# SysController.net
KiCad netlist of a schematic drawn in Altium Designer
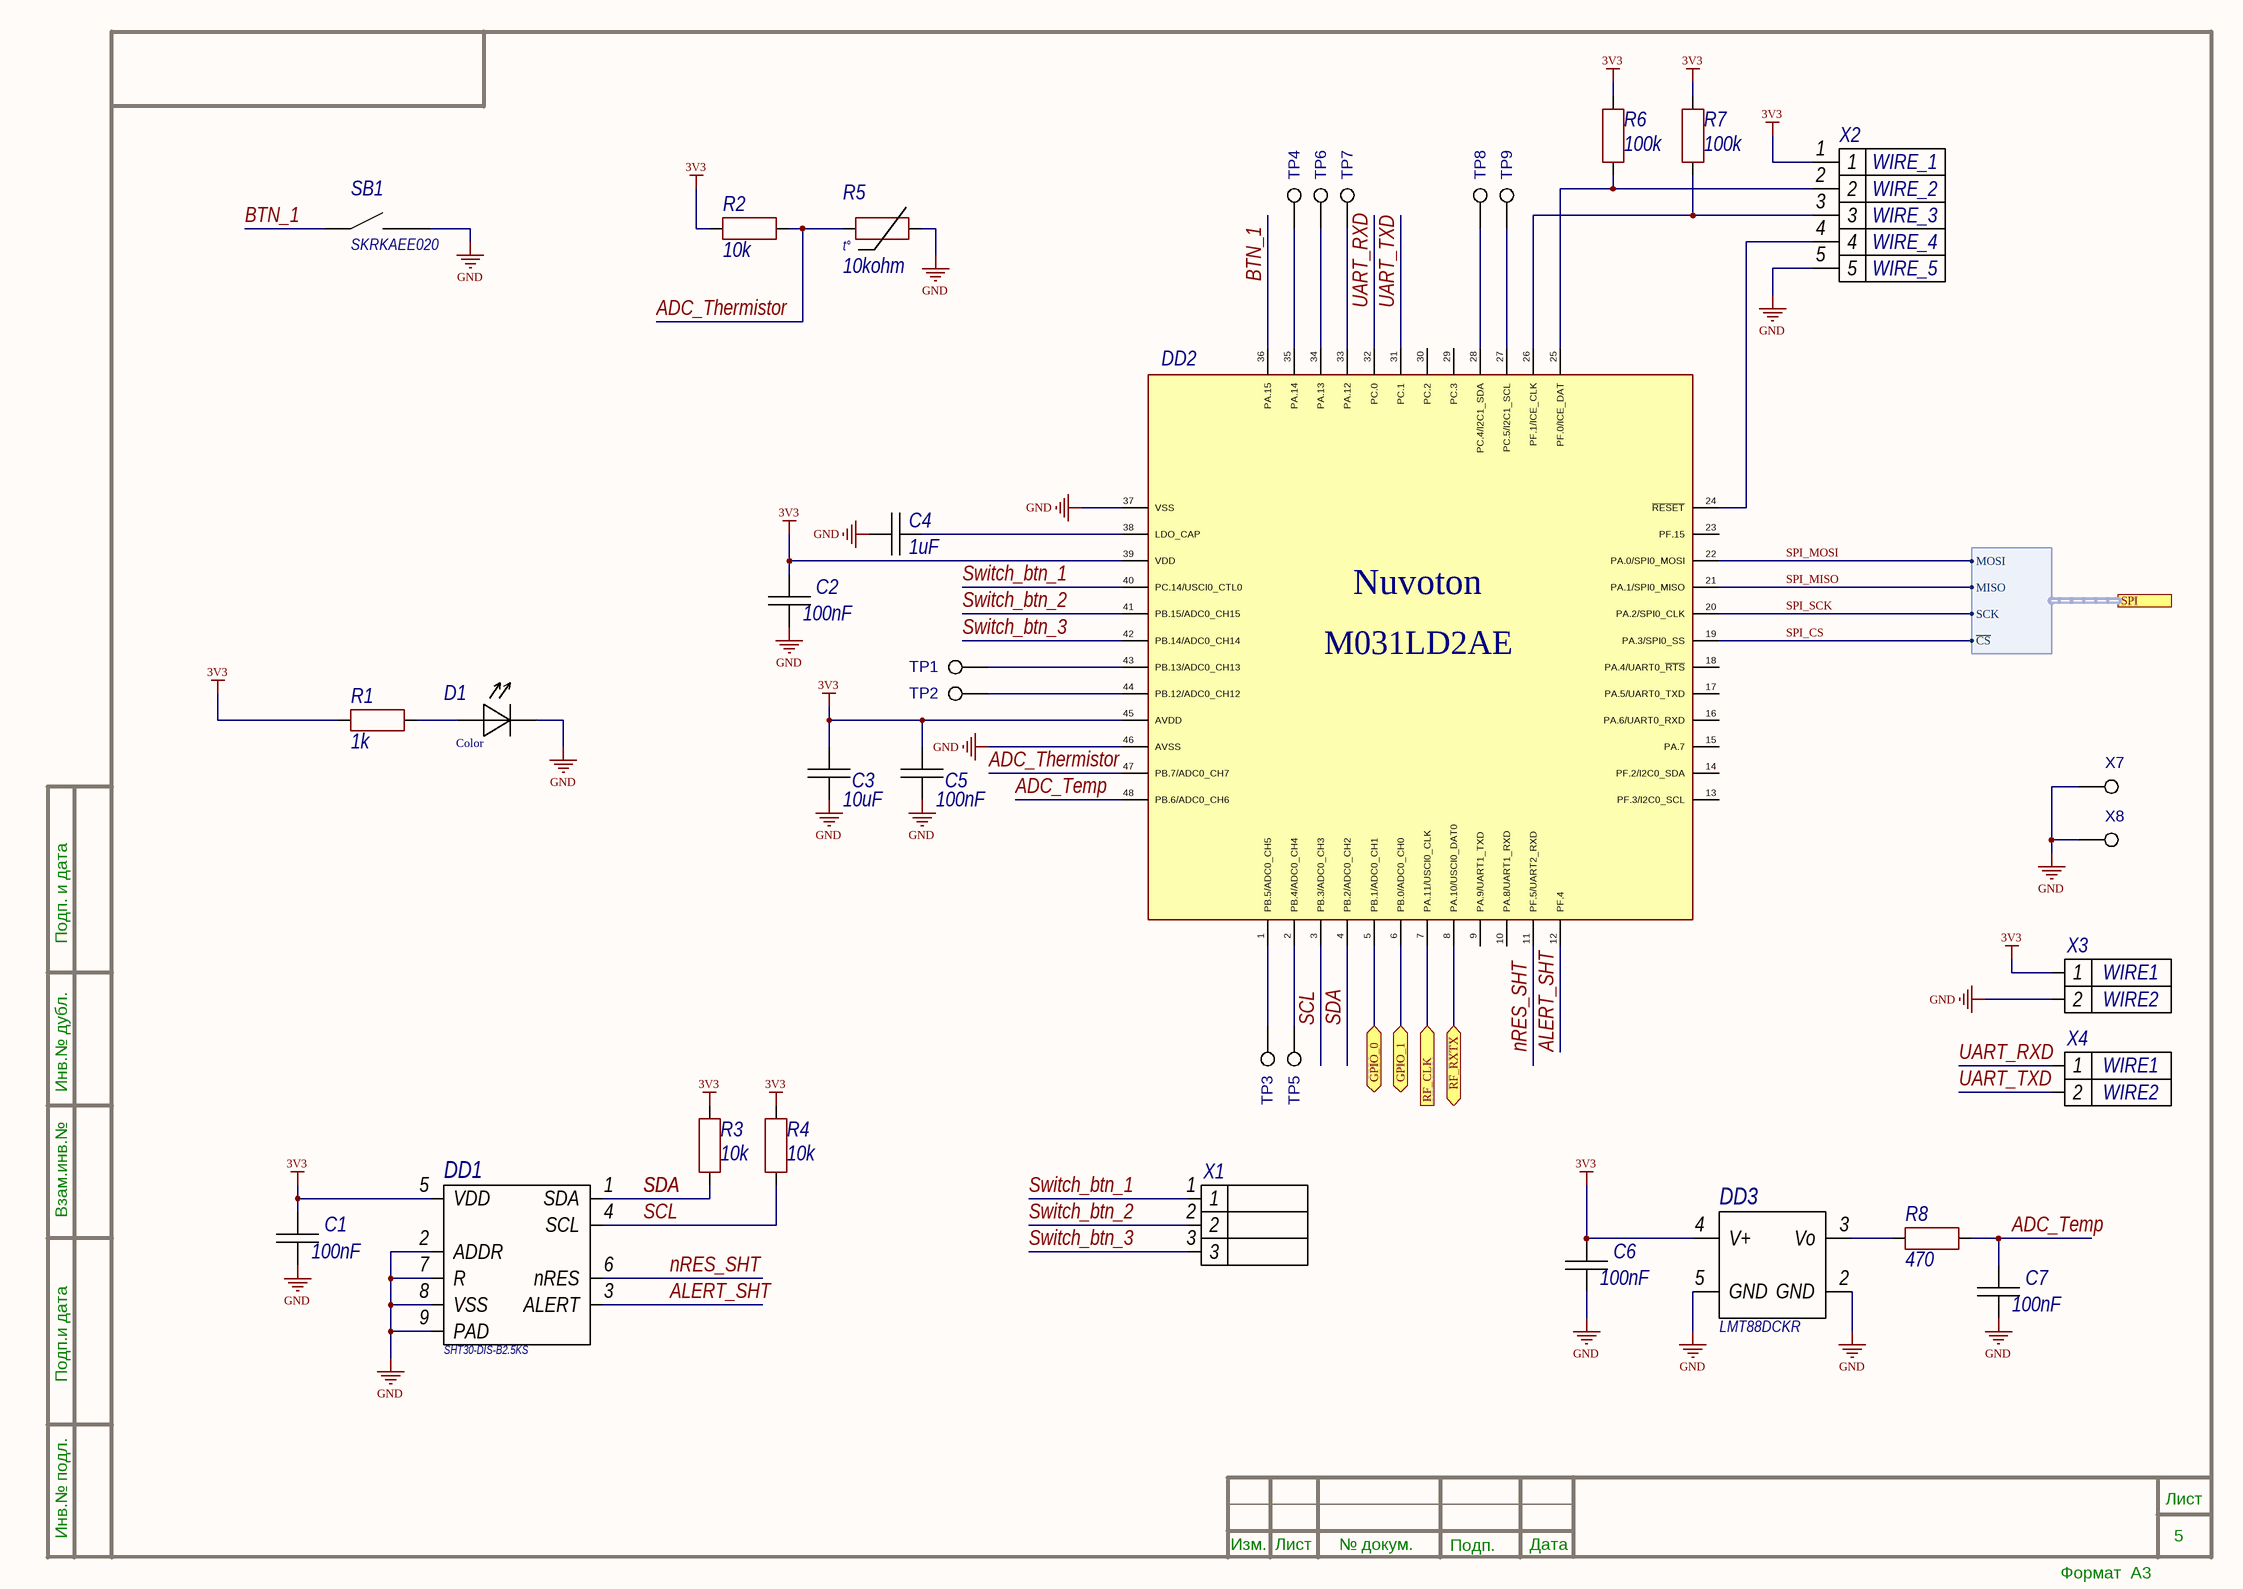
[diagram p0: SysController.SchDoc]

(export (version "E")
  (design (tool "Eeschema 10.0.6"))
  (components
    (comp (ref "C1")
      (value "100nF")
      (footprint "CAP0402")
      (fields (field (name "PART NUMBER") "CAP0402") (field (name "Comment") "100nF "))
      (libsource (lib "Library") (part "CAPC"))
    )
    (comp (ref "C2")
      (value "100nF")
      (footprint "CAP0402")
      (fields (field (name "PART NUMBER") "CAP0402") (field (name "Comment") "100nF "))
      (libsource (lib "Library") (part "CAPC"))
    )
    (comp (ref "C3")
      (value "10uF")
      (footprint "CAPC0603N")
      (fields (field (name "PART NUMBER") "CAPC") (field (name "Comment") "10uF "))
      (libsource (lib "Library") (part "CAPC"))
    )
    (comp (ref "C4")
      (value "1uF")
      (footprint "CAPC0603N")
      (fields (field (name "PART NUMBER") "CAPC") (field (name "Comment") "1uF "))
      (libsource (lib "Library") (part "CAPC"))
    )
    (comp (ref "C5")
      (value "100nF")
      (footprint "CAP0402")
      (fields (field (name "PART NUMBER") "CAP0402") (field (name "Comment") "100nF "))
      (libsource (lib "Library") (part "CAPC"))
    )
    (comp (ref "C6")
      (value "100nF")
      (footprint "CAP0402")
      (fields (field (name "PART NUMBER") "CAP0402") (field (name "Comment") "100nF "))
      (libsource (lib "Library") (part "CAPC"))
    )
    (comp (ref "C7")
      (value "100nF")
      (footprint "CAP0402")
      (fields (field (name "PART NUMBER") "CAP0402") (field (name "Comment") "100nF "))
      (libsource (lib "Library") (part "CAPC"))
    )
    (comp (ref "D1")
      (value "Color")
      (footprint "LED603")
      (fields (field (name "PART NUMBER") "LEDC"))
      (libsource (lib "Library") (part "LEDC"))
    )
    (comp (ref "DD1")
      (value "SHT30-DIS-B2.5KS")
      (footprint "DFN8")
      (fields (field (name "MPN") "SHT30-DIS-B2.5KS") (field (name "MANUFACTURER") "SENSIRION"))
      (libsource (lib "Library") (part "DD_SHTxx"))
    )
    (comp (ref "DD2")
      (value "~")
      (footprint "LQFP48")
      (fields (field (name "PART NUMBER") "M031LD2AE") (field (name "MANUFACTURER") "Nuvoton"))
      (libsource (lib "Library") (part "M031LD2AE"))
    )
    (comp (ref "DD3")
      (value "~")
      (footprint "SC70-5")
      (fields
        (field (name "MPN") "LMT88DCKR")
        (field (name "PART NUMBER") "LMT88DCKR")
        (field (name "MANUFACTURER") "TI")
      )
      (libsource (lib "Library") (part "DD_LMT88"))
    )
    (comp (ref "R1")
      (value "1k")
      (footprint "RESC0402(1005)_M")
      (fields (field (name "PART NUMBER") "RES0402") (field (name "Comment") "1k "))
      (libsource (lib "Library") (part "RES"))
    )
    (comp (ref "R2")
      (value "10k")
      (footprint "RESC0402(1005)_M")
      (fields (field (name "PART NUMBER") "RES0402") (field (name "Comment") "10k "))
      (libsource (lib "Library") (part "RES"))
    )
    (comp (ref "R3")
      (value "10k")
      (footprint "RESC0402(1005)_M")
      (fields (field (name "PART NUMBER") "RES0402") (field (name "Comment") "10k "))
      (libsource (lib "") (part "RES_1"))
    )
    (comp (ref "R4")
      (value "10k")
      (footprint "RESC0402(1005)_M")
      (fields (field (name "PART NUMBER") "RES0402") (field (name "Comment") "10k "))
      (libsource (lib "") (part "RES_1"))
    )
    (comp (ref "R5")
      (value "10kohm")
      (footprint "RESC0805L")
      (fields
        (field (name "PART NUMBER") "SDNT2012X103F3950FTF")
        (field (name "MANUFACTURER") "Sunlord")
        (field (name "Comment") "10kohm ")
      )
      (libsource (lib "Library") (part "RES_Thermo"))
    )
    (comp (ref "R6")
      (value "100k")
      (footprint "RESC0402(1005)_M")
      (fields (field (name "PART NUMBER") "RES0402") (field (name "Comment") "100k "))
      (libsource (lib "") (part "RES_1"))
    )
    (comp (ref "R7")
      (value "100k")
      (footprint "RESC0402(1005)_M")
      (fields (field (name "PART NUMBER") "RES0402") (field (name "Comment") "100k "))
      (libsource (lib "") (part "RES_1"))
    )
    (comp (ref "R8")
      (value "470")
      (footprint "RESC0402(1005)_M")
      (fields (field (name "PART NUMBER") "RES0402") (field (name "Comment") "470 "))
      (libsource (lib "Library") (part "RES"))
    )
    (comp (ref "SB1")
      (value "DTSM-3")
      (footprint "SW_SKRKAEE020")
      (fields (field (name "MPN") "SKRKAEE020") (field (name "PART NUMBER") "SKRKAEE020"))
      (libsource (lib "Library") (part "DTSM-3"))
    )
    (comp (ref "TP1")
      (value "TP-SINGLE-ROUND")
      (footprint "TP-ROUND-TOP-1.5")
      (libsource (lib "Library") (part "TP-SINGLE-ROUND"))
    )
    (comp (ref "TP2")
      (value "TP-SINGLE-ROUND")
      (footprint "TP-ROUND-TOP-1.5")
      (libsource (lib "Library") (part "TP-SINGLE-ROUND"))
    )
    (comp (ref "TP3")
      (value "TP-SINGLE-ROUND")
      (footprint "TP-ROUND-TOP-1.5")
      (libsource (lib "Library") (part "TP-SINGLE-ROUND"))
    )
    (comp (ref "TP4")
      (value "TP-SINGLE-ROUND")
      (footprint "TP-ROUND-TOP-1.5")
      (libsource (lib "Library") (part "TP-SINGLE-ROUND"))
    )
    (comp (ref "TP5")
      (value "TP-SINGLE-ROUND")
      (footprint "TP-ROUND-TOP-1.5")
      (libsource (lib "Library") (part "TP-SINGLE-ROUND"))
    )
    (comp (ref "TP6")
      (value "TP-SINGLE-ROUND")
      (footprint "TP-ROUND-TOP-1.5")
      (libsource (lib "Library") (part "TP-SINGLE-ROUND"))
    )
    (comp (ref "TP7")
      (value "TP-SINGLE-ROUND")
      (footprint "TP-ROUND-TOP-1.5")
      (libsource (lib "Library") (part "TP-SINGLE-ROUND"))
    )
    (comp (ref "TP8")
      (value "TP-SINGLE-ROUND")
      (footprint "TP-ROUND-TOP-1.5")
      (libsource (lib "Library") (part "TP-SINGLE-ROUND"))
    )
    (comp (ref "TP9")
      (value "TP-SINGLE-ROUND")
      (footprint "TP-ROUND-TOP-1.5")
      (libsource (lib "Library") (part "TP-SINGLE-ROUND"))
    )
    (comp (ref "X1")
      (value "PLS-3")
      (footprint "SmartHome_for_switch")
      (fields (field (name "PART NUMBER") "SmartHome_for_switch"))
      (libsource (lib "Library") (part "Connector_3pin"))
    )
    (comp (ref "X2")
      (value "PLS5")
      (footprint "PLS5")
      (fields
        (field (name "WIRE5") "WIRE_5")
        (field (name "WIRE4") "WIRE_4")
        (field (name "WIRE3") "WIRE_3")
        (field (name "WIRE2") "WIRE_2")
        (field (name "WIRE1") "WIRE_1")
      )
      (libsource (lib "Library") (part "PLS5"))
    )
    (comp (ref "X3")
      (value "DG350-3.5-02P-14-00A")
      (footprint "Conn_3,5mm_2pin")
      (fields (field (name "WIRE2") "WIRE2") (field (name "WIRE1") "WIRE1"))
      (libsource (lib "Library") (part "Connector_2pin"))
    )
    (comp (ref "X4")
      (value "DG350-3.5-02P-14-00A")
      (footprint "Conn_3,5mm_2pin")
      (fields (field (name "WIRE2") "WIRE2") (field (name "WIRE1") "WIRE1"))
      (libsource (lib "Library") (part "Connector_2pin"))
    )
    (comp (ref "X7")
      (value "PLS1")
      (footprint "PLS1")
      (fields (field (name "PART NUMBER") "Test_PLS1"))
      (libsource (lib "Library") (part "PAD-CONNECT-MINI"))
    )
    (comp (ref "X8")
      (value "PLS1")
      (footprint "PLS1")
      (fields (field (name "PART NUMBER") "Test_PLS1"))
      (libsource (lib "Library") (part "PAD-CONNECT-MINI"))
    )
  )
  (nets
    (net (code "2") (name "/ADC_Temp") (class "Default")
      (node (ref "C7") (pin "2") (pinfunction "2_2") (pintype "passive"))
      (node (ref "DD2") (pin "48") (pinfunction "PB.6/ADC0_CH6_48") (pintype "passive"))
      (node (ref "R8") (pin "2") (pinfunction "2_2") (pintype "passive"))
    )
    (net (code "3") (name "/ADC_Thermistor") (class "Default")
      (node (ref "DD2") (pin "47") (pinfunction "PB.7/ADC0_CH7_47") (pintype "passive"))
      (node (ref "R2") (pin "2") (pinfunction "2_2") (pintype "passive"))
      (node (ref "R5") (pin "1") (pinfunction "1_1") (pintype "passive"))
    )
    (net (code "4") (name "/ALERT_SHT") (class "Default")
      (node (ref "DD1") (pin "3") (pinfunction "ALERT_3") (pintype "passive"))
      (node (ref "DD2") (pin "12") (pinfunction "PF.4_12") (pintype "passive"))
    )
    (net (code "5") (name "/BTN_1") (class "Default")
      (node (ref "DD2") (pin "36") (pinfunction "PA.15_36") (pintype "passive"))
      (node (ref "SB1") (pin "2") (pinfunction "2_2") (pintype "passive"))
    )
    (net (code "6") (name "/GPIO_0") (class "Default")
      (node (ref "DD2") (pin "5") (pinfunction "PB.1/ADC0_CH1_5") (pintype "passive"))
    )
    (net (code "7") (name "/GPIO_1") (class "Default")
      (node (ref "DD2") (pin "6") (pinfunction "PB.0/ADC0_CH0_6") (pintype "passive"))
    )
    (net (code "8") (name "/RF_CLK") (class "Default")
      (node (ref "DD2") (pin "7") (pinfunction "PA.11/USCI0_CLK_7") (pintype "passive"))
    )
    (net (code "9") (name "/RF_RXTX") (class "Default")
      (node (ref "DD2") (pin "8") (pinfunction "PA.10/USCI0_DAT0_8") (pintype "passive"))
    )
    (net (code "10") (name "/SCL") (class "Default")
      (node (ref "DD1") (pin "4") (pinfunction "SCL_4") (pintype "passive"))
      (node (ref "DD2") (pin "3") (pinfunction "PB.3/ADC0_CH3_3") (pintype "passive"))
      (node (ref "R4") (pin "1") (pinfunction "1_1") (pintype "passive"))
    )
    (net (code "11") (name "/SDA") (class "Default")
      (node (ref "DD1") (pin "1") (pinfunction "SDA_1") (pintype "passive"))
      (node (ref "DD2") (pin "4") (pinfunction "PB.2/ADC0_CH2_4") (pintype "passive"))
      (node (ref "R3") (pin "1") (pinfunction "1_1") (pintype "passive"))
    )
    (net (code "12") (name "/SPI_CS") (class "Default")
      (node (ref "DD2") (pin "19") (pinfunction "PA.3/SPI0_SS_19") (pintype "passive"))
    )
    (net (code "13") (name "/SPI_MISO") (class "Default")
      (node (ref "DD2") (pin "21") (pinfunction "PA.1/SPI0_MISO_21") (pintype "passive"))
    )
    (net (code "14") (name "/SPI_MOSI") (class "Default")
      (node (ref "DD2") (pin "22") (pinfunction "PA.0/SPI0_MOSI_22") (pintype "passive"))
    )
    (net (code "15") (name "/SPI_SCK") (class "Default")
      (node (ref "DD2") (pin "20") (pinfunction "PA.2/SPI0_CLK_20") (pintype "passive"))
    )
    (net (code "16") (name "/Switch_btn_1") (class "Default")
      (node (ref "DD2") (pin "40") (pinfunction "PC.14/USCI0_CTL0_40") (pintype "passive"))
      (node (ref "X1") (pin "1") (pinfunction "1_1") (pintype "passive"))
    )
    (net (code "17") (name "/Switch_btn_2") (class "Default")
      (node (ref "DD2") (pin "41") (pinfunction "PB.15/ADC0_CH15_41") (pintype "passive"))
      (node (ref "X1") (pin "2") (pinfunction "2_2") (pintype "passive"))
    )
    (net (code "18") (name "/Switch_btn_3") (class "Default")
      (node (ref "DD2") (pin "42") (pinfunction "PB.14/ADC0_CH14_42") (pintype "passive"))
      (node (ref "X1") (pin "3") (pinfunction "3_3") (pintype "passive"))
    )
    (net (code "19") (name "/UART_RXD") (class "Default")
      (node (ref "DD2") (pin "32") (pinfunction "PC.0_32") (pintype "passive"))
      (node (ref "X4") (pin "1") (pinfunction "1_1") (pintype "passive"))
    )
    (net (code "20") (name "/UART_TXD") (class "Default")
      (node (ref "DD2") (pin "31") (pinfunction "PC.1_31") (pintype "passive"))
      (node (ref "X4") (pin "2") (pinfunction "2_2") (pintype "passive"))
    )
    (net (code "21") (name "/nRES_SHT") (class "Default")
      (node (ref "DD1") (pin "6") (pinfunction "nRES_6") (pintype "passive"))
      (node (ref "DD2") (pin "11") (pinfunction "PF.5/UART2_RXD_11") (pintype "passive"))
    )
    (net (code "23") (name "3V3") (class "Default")
      (node (ref "C1") (pin "2") (pinfunction "2_2") (pintype "passive"))
      (node (ref "C2") (pin "2") (pinfunction "2_2") (pintype "passive"))
      (node (ref "C3") (pin "1") (pinfunction "1_1") (pintype "passive"))
      (node (ref "C5") (pin "2") (pinfunction "2_2") (pintype "passive"))
      (node (ref "C6") (pin "2") (pinfunction "2_2") (pintype "passive"))
      (node (ref "DD1") (pin "5") (pinfunction "VDD_5") (pintype "passive"))
      (node (ref "DD2") (pin "39") (pinfunction "VDD_39") (pintype "power_in"))
      (node (ref "DD2") (pin "45") (pinfunction "AVDD_45") (pintype "power_in"))
      (node (ref "DD3") (pin "4") (pinfunction "V+_4") (pintype "passive"))
      (node (ref "R1") (pin "1") (pinfunction "1_1") (pintype "passive"))
      (node (ref "R2") (pin "1") (pinfunction "1_1") (pintype "passive"))
      (node (ref "R3") (pin "2") (pinfunction "2_2") (pintype "passive"))
      (node (ref "R4") (pin "2") (pinfunction "2_2") (pintype "passive"))
      (node (ref "R6") (pin "2") (pinfunction "2_2") (pintype "passive"))
      (node (ref "R7") (pin "2") (pinfunction "2_2") (pintype "passive"))
      (node (ref "X2") (pin "1") (pinfunction "1_1") (pintype "passive"))
      (node (ref "X3") (pin "1") (pinfunction "1_1") (pintype "passive"))
    )
    (net (code "24") (name "GND") (class "Default")
      (node (ref "C1") (pin "1") (pinfunction "1_1") (pintype "passive"))
      (node (ref "C2") (pin "1") (pinfunction "1_1") (pintype "passive"))
      (node (ref "C3") (pin "2") (pinfunction "2_2") (pintype "passive"))
      (node (ref "C4") (pin "1") (pinfunction "1_1") (pintype "passive"))
      (node (ref "C5") (pin "1") (pinfunction "1_1") (pintype "passive"))
      (node (ref "C6") (pin "1") (pinfunction "1_1") (pintype "passive"))
      (node (ref "C7") (pin "1") (pinfunction "1_1") (pintype "passive"))
      (node (ref "D1") (pin "1") (pinfunction "A_1") (pintype "passive"))
      (node (ref "DD1") (pin "2") (pinfunction "ADDR_2") (pintype "passive"))
      (node (ref "DD1") (pin "7") (pinfunction "R_7") (pintype "passive"))
      (node (ref "DD1") (pin "8") (pinfunction "VSS_8") (pintype "passive"))
      (node (ref "DD1") (pin "9") (pinfunction "PAD_9") (pintype "passive"))
      (node (ref "DD2") (pin "37") (pinfunction "VSS_37") (pintype "power_in"))
      (node (ref "DD2") (pin "46") (pinfunction "AVSS_46") (pintype "power_in"))
      (node (ref "DD3") (pin "2") (pinfunction "GND_2") (pintype "passive"))
      (node (ref "DD3") (pin "5") (pinfunction "GND_5") (pintype "passive"))
      (node (ref "R5") (pin "2") (pinfunction "2_2") (pintype "passive"))
      (node (ref "SB1") (pin "1") (pinfunction "1_1") (pintype "passive"))
      (node (ref "X2") (pin "5") (pinfunction "5_5") (pintype "passive"))
      (node (ref "X3") (pin "2") (pinfunction "2_2") (pintype "passive"))
      (node (ref "X7") (pin "1") (pinfunction "1_1") (pintype "passive"))
      (node (ref "X8") (pin "1") (pinfunction "1_1") (pintype "passive"))
    )
    (net (code "25") (name "Net-(D1-K)") (class "Default")
      (node (ref "D1") (pin "2") (pinfunction "K_2") (pintype "passive"))
      (node (ref "R1") (pin "2") (pinfunction "2_2") (pintype "passive"))
    )
    (net (code "26") (name "Net-(DD2-LDO_CAP)") (class "Default")
      (node (ref "C4") (pin "2") (pinfunction "2_2") (pintype "passive"))
      (node (ref "DD2") (pin "38") (pinfunction "LDO_CAP_38") (pintype "power_in"))
    )
    (net (code "27") (name "Net-(DD2-PA.12)") (class "Default")
      (node (ref "DD2") (pin "33") (pinfunction "PA.12_33") (pintype "passive"))
      (node (ref "TP7") (pin "1") (pinfunction "1_1") (pintype "passive"))
    )
    (net (code "28") (name "Net-(DD2-PA.13)") (class "Default")
      (node (ref "DD2") (pin "34") (pinfunction "PA.13_34") (pintype "passive"))
      (node (ref "TP6") (pin "1") (pinfunction "1_1") (pintype "passive"))
    )
    (net (code "29") (name "Net-(DD2-PA.14)") (class "Default")
      (node (ref "DD2") (pin "35") (pinfunction "PA.14_35") (pintype "passive"))
      (node (ref "TP4") (pin "1") (pinfunction "1_1") (pintype "passive"))
    )
    (net (code "30") (name "Net-(DD2-PB.4{slash}ADC0_CH4)") (class "Default")
      (node (ref "DD2") (pin "2") (pinfunction "PB.4/ADC0_CH4_2") (pintype "passive"))
      (node (ref "TP5") (pin "1") (pinfunction "1_1") (pintype "passive"))
    )
    (net (code "31") (name "Net-(DD2-PB.5{slash}ADC0_CH5)") (class "Default")
      (node (ref "DD2") (pin "1") (pinfunction "PB.5/ADC0_CH5_1") (pintype "passive"))
      (node (ref "TP3") (pin "1") (pinfunction "1_1") (pintype "passive"))
    )
    (net (code "32") (name "Net-(DD2-PB.12{slash}ADC0_CH12)") (class "Default")
      (node (ref "DD2") (pin "44") (pinfunction "PB.12/ADC0_CH12_44") (pintype "passive"))
      (node (ref "TP2") (pin "1") (pinfunction "1_1") (pintype "passive"))
    )
    (net (code "33") (name "Net-(DD2-PB.13{slash}ADC0_CH13)") (class "Default")
      (node (ref "DD2") (pin "43") (pinfunction "PB.13/ADC0_CH13_43") (pintype "passive"))
      (node (ref "TP1") (pin "1") (pinfunction "1_1") (pintype "passive"))
    )
    (net (code "34") (name "Net-(DD2-PC.4{slash}I2C1_SDA)") (class "Default")
      (node (ref "DD2") (pin "28") (pinfunction "PC.4/I2C1_SDA_28") (pintype "passive"))
      (node (ref "TP8") (pin "1") (pinfunction "1_1") (pintype "passive"))
    )
    (net (code "35") (name "Net-(DD2-PC.5{slash}I2C1_SCL)") (class "Default")
      (node (ref "DD2") (pin "27") (pinfunction "PC.5/I2C1_SCL_27") (pintype "passive"))
      (node (ref "TP9") (pin "1") (pinfunction "1_1") (pintype "passive"))
    )
    (net (code "36") (name "Net-(DD2-PF.0{slash}ICE_DAT)") (class "Default")
      (node (ref "DD2") (pin "25") (pinfunction "PF.0/ICE_DAT_25") (pintype "passive"))
      (node (ref "R6") (pin "1") (pinfunction "1_1") (pintype "passive"))
      (node (ref "X2") (pin "2") (pinfunction "2_2") (pintype "passive"))
    )
    (net (code "37") (name "Net-(DD2-PF.1{slash}ICE_CLK)") (class "Default")
      (node (ref "DD2") (pin "26") (pinfunction "PF.1/ICE_CLK_26") (pintype "passive"))
      (node (ref "R7") (pin "1") (pinfunction "1_1") (pintype "passive"))
      (node (ref "X2") (pin "3") (pinfunction "3_3") (pintype "passive"))
    )
    (net (code "38") (name "Net-(DD2-~{RESET})") (class "Default")
      (node (ref "DD2") (pin "24") (pinfunction "~{RESET}_24") (pintype "passive"))
      (node (ref "X2") (pin "4") (pinfunction "4_4") (pintype "passive"))
    )
    (net (code "39") (name "Net-(DD3-Vo)") (class "Default")
      (node (ref "DD3") (pin "3") (pinfunction "Vo_3") (pintype "passive"))
      (node (ref "R8") (pin "1") (pinfunction "1_1") (pintype "passive"))
    )
    (net (code "40") (name "unconnected-(DD2-PA.4{slash}UART0_~{RTS}-Pad18)") (class "Default")
      (node (ref "DD2") (pin "18") (pinfunction "PA.4/UART0_~{RTS}_18") (pintype "passive"))
    )
    (net (code "41") (name "unconnected-(DD2-PA.5{slash}UART0_TXD-Pad17)") (class "Default")
      (node (ref "DD2") (pin "17") (pinfunction "PA.5/UART0_TXD_17") (pintype "passive"))
    )
    (net (code "42") (name "unconnected-(DD2-PA.6{slash}UART0_RXD-Pad16)") (class "Default")
      (node (ref "DD2") (pin "16") (pinfunction "PA.6/UART0_RXD_16") (pintype "passive"))
    )
    (net (code "43") (name "unconnected-(DD2-PA.7-Pad15)") (class "Default")
      (node (ref "DD2") (pin "15") (pinfunction "PA.7_15") (pintype "passive"))
    )
    (net (code "44") (name "unconnected-(DD2-PA.8{slash}UART1_RXD-Pad10)") (class "Default")
      (node (ref "DD2") (pin "10") (pinfunction "PA.8/UART1_RXD_10") (pintype "passive"))
    )
    (net (code "45") (name "unconnected-(DD2-PA.9{slash}UART1_TXD-Pad9)") (class "Default")
      (node (ref "DD2") (pin "9") (pinfunction "PA.9/UART1_TXD_9") (pintype "passive"))
    )
    (net (code "46") (name "unconnected-(DD2-PC.2-Pad30)") (class "Default")
      (node (ref "DD2") (pin "30") (pinfunction "PC.2_30") (pintype "passive"))
    )
    (net (code "47") (name "unconnected-(DD2-PC.3-Pad29)") (class "Default")
      (node (ref "DD2") (pin "29") (pinfunction "PC.3_29") (pintype "passive"))
    )
    (net (code "48") (name "unconnected-(DD2-PF.2{slash}I2C0_SDA-Pad14)") (class "Default")
      (node (ref "DD2") (pin "14") (pinfunction "PF.2/I2C0_SDA_14") (pintype "passive"))
    )
    (net (code "49") (name "unconnected-(DD2-PF.3{slash}I2C0_SCL-Pad13)") (class "Default")
      (node (ref "DD2") (pin "13") (pinfunction "PF.3/I2C0_SCL_13") (pintype "passive"))
    )
    (net (code "50") (name "unconnected-(DD2-PF.15-Pad23)") (class "Default")
      (node (ref "DD2") (pin "23") (pinfunction "PF.15_23") (pintype "passive"))
    )
  )
)
